# mcu.net
KiCad netlist of a schematic drawn in Altium Designer
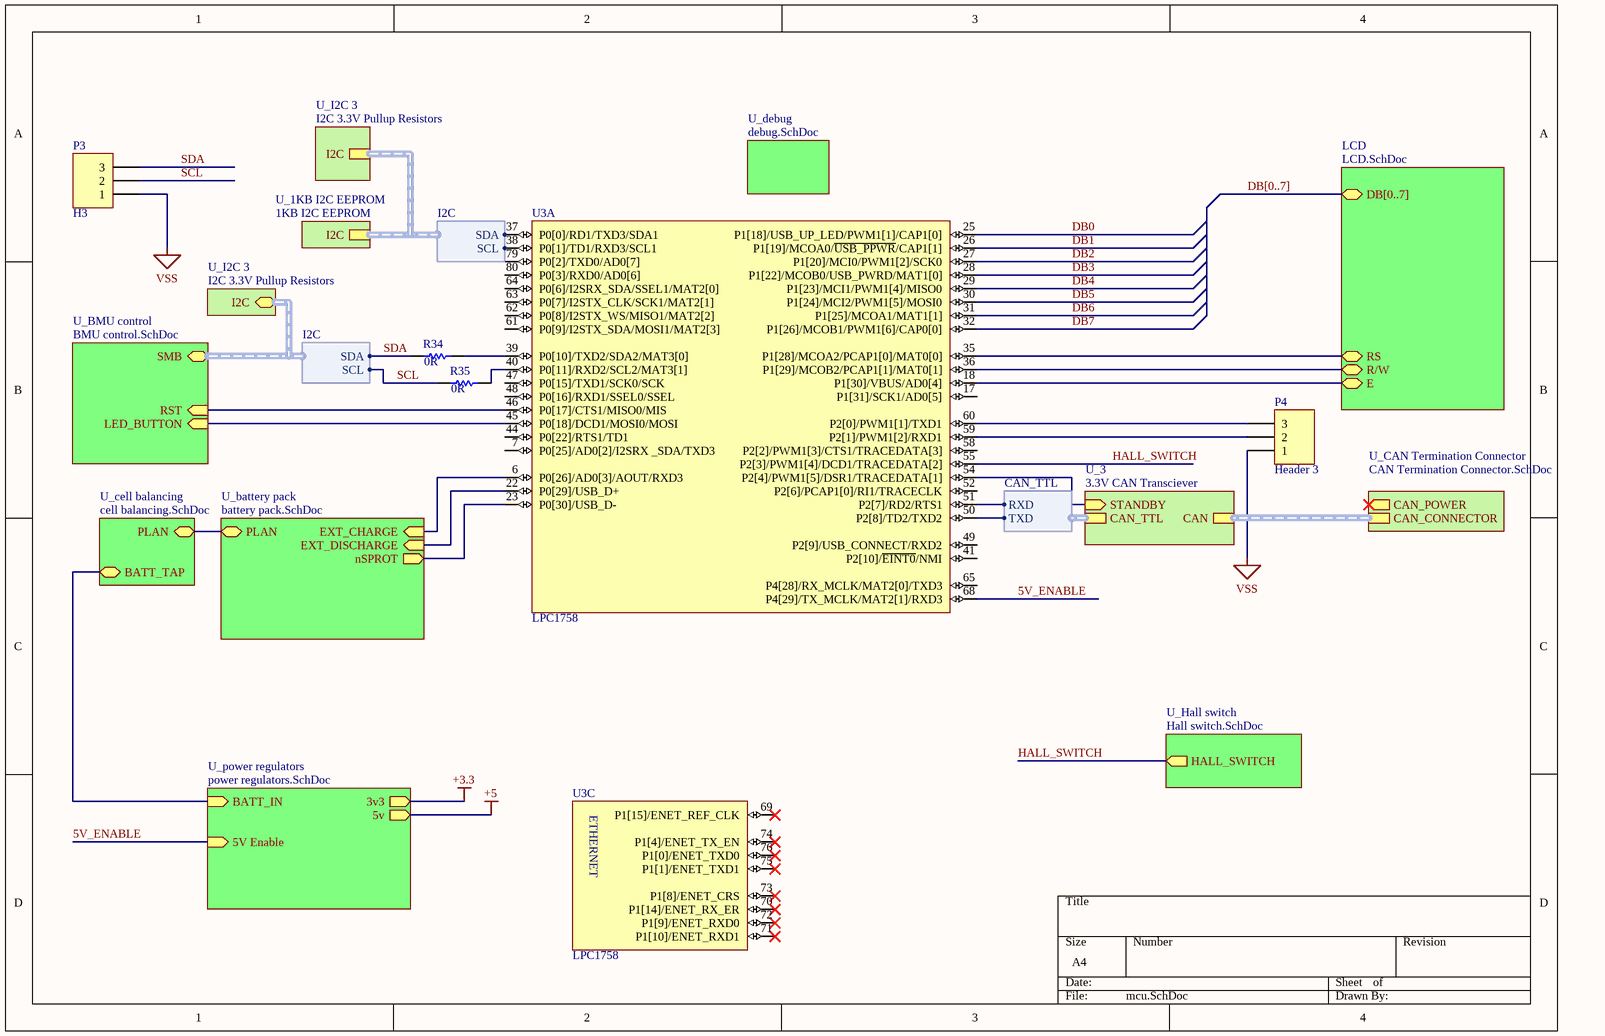
[diagram p0: mcu.SchDoc]

(export (version "E")
  (design (tool "Eeschema 10.0.6"))
  (components
    (comp (ref "P3")
      (value "H3")
      (footprint "HDR1X3")
      (description "Header, 3-Pin")
      (fields (field (name "PUBLISHER") "Altium Limited"))
      (libsource (lib "TXS0108E") (part "TXS0108E"))
    )
    (comp (ref "P4")
      (value "Header 3")
      (footprint "HDR1X3")
      (description "Header, 3-Pin")
      (fields (field (name "PUBLISHER") "Altium Limited"))
      (libsource (lib "Miscellaneous Connectors") (part "Header 3"))
    )
    (comp (ref "R34")
      (value "0R")
      (footprint "R0603")
      (description "Resistor")
      (fields (field (name "Comment") "Res1") (field (name "PUBLISHER") "Altium Limited"))
      (libsource (lib "Miscellaneous Devices") (part "Res1"))
    )
    (comp (ref "R35")
      (value "0R")
      (footprint "R0603")
      (description "Resistor")
      (fields (field (name "Comment") "Res1") (field (name "PUBLISHER") "Altium Limited"))
      (libsource (lib "Miscellaneous Devices") (part "Res1"))
    )
    (comp (ref "U3")
      (value "LPC1758")
      (footprint "LPC1758FBD80")
      (description "NXP - LPC1758FBD80 - MCU, 32BIT, ARM CORTEX M3, 80LQFP")
      (libsource (lib "LPC1758") (part "LPC1758"))
    )
  )
  (nets
    (net (code "5") (name "/5V_ENABLE") (class "Default")
      (node (ref "U3") (pin "68") (pinfunction "P4[29]/TX_MCLK/MAT2[1]/RXD3_68") (pintype "bidirectional"))
    )
    (net (code "9") (name "/DB0") (class "Default")
      (node (ref "U3") (pin "25") (pinfunction "P1[18]/USB_UP_LED/PWM1[1]/CAP1[0]_25") (pintype "bidirectional"))
    )
    (net (code "10") (name "/DB1") (class "Default")
      (node (ref "U3") (pin "26") (pinfunction "P1[19]/MCOA0/~{USB_PPWR}/CAP1[1]_26") (pintype "bidirectional"))
    )
    (net (code "11") (name "/DB2") (class "Default")
      (node (ref "U3") (pin "27") (pinfunction "P1[20]/MCI0/PWM1[2]/SCK0_27") (pintype "bidirectional"))
    )
    (net (code "12") (name "/DB3") (class "Default")
      (node (ref "U3") (pin "28") (pinfunction "P1[22]/MCOB0/USB_PWRD/MAT1[0]_28") (pintype "bidirectional"))
    )
    (net (code "13") (name "/DB4") (class "Default")
      (node (ref "U3") (pin "29") (pinfunction "P1[23]/MCI1/PWM1[4]/MISO0_29") (pintype "bidirectional"))
    )
    (net (code "14") (name "/DB5") (class "Default")
      (node (ref "U3") (pin "30") (pinfunction "P1[24]/MCI2/PWM1[5]/MOSI0_30") (pintype "bidirectional"))
    )
    (net (code "15") (name "/DB6") (class "Default")
      (node (ref "U3") (pin "31") (pinfunction "P1[25]/MCOA1/MAT1[1]_31") (pintype "bidirectional"))
    )
    (net (code "16") (name "/DB7") (class "Default")
      (node (ref "U3") (pin "32") (pinfunction "P1[26]/MCOB1/PWM1[6]/CAP0[0]_32") (pintype "bidirectional"))
    )
    (net (code "18") (name "/E") (class "Default")
      (node (ref "U3") (pin "18") (pinfunction "P1[30]/VBUS/AD0[4]_18") (pintype "bidirectional"))
    )
    (net (code "19") (name "/EXT_CHARGE") (class "Default")
      (node (ref "U3") (pin "6") (pinfunction "P0[26]/AD0[3]/AOUT/RXD3_6") (pintype "bidirectional"))
    )
    (net (code "20") (name "/EXT_DISCHARGE") (class "Default")
      (node (ref "U3") (pin "22") (pinfunction "P0[29]/USB_D+_22") (pintype "bidirectional"))
    )
    (net (code "21") (name "/HALL_SWITCH") (class "Default")
      (node (ref "U3") (pin "55") (pinfunction "P2[3]/PWM1[4]/DCD1/TRACEDATA[2]_55") (pintype "bidirectional"))
    )
    (net (code "24") (name "/LED_BUTTON") (class "Default")
      (node (ref "U3") (pin "45") (pinfunction "P0[18]/DCD1/MOSI0/MOSI_45") (pintype "bidirectional"))
    )
    (net (code "26") (name "/RS") (class "Default")
      (node (ref "U3") (pin "35") (pinfunction "P1[28]/MCOA2/PCAP1[0]/MAT0[0]_35") (pintype "bidirectional"))
    )
    (net (code "27") (name "/RST") (class "Default")
      (node (ref "U3") (pin "46") (pinfunction "P0[17]/CTS1/MISO0/MIS_46") (pintype "bidirectional"))
    )
    (net (code "28") (name "/RXD") (class "Default")
      (node (ref "U3") (pin "51") (pinfunction "P2[7]/RD2/RTS1_51") (pintype "bidirectional"))
    )
    (net (code "29") (name "/R{slash}W") (class "Default")
      (node (ref "U3") (pin "36") (pinfunction "P1[29]/MCOB2/PCAP1[1]/MAT0[1]_36") (pintype "bidirectional"))
    )
    (net (code "30") (name "/SCL") (class "Default")
      (node (ref "P3") (pin "2") (pinfunction "2_2") (pintype "passive"))
      (node (ref "R35") (pin "1") (pinfunction "1_1") (pintype "passive"))
    )
    (net (code "31") (name "/SDA") (class "Default")
      (node (ref "P3") (pin "3") (pinfunction "3_3") (pintype "passive"))
      (node (ref "R34") (pin "1") (pinfunction "1_1") (pintype "passive"))
    )
    (net (code "32") (name "/STANDBY") (class "Default")
      (node (ref "U3") (pin "54") (pinfunction "P2[4]/PWM1[5]/DSR1/TRACEDATA[1]_54") (pintype "bidirectional"))
    )
    (net (code "33") (name "/TXD") (class "Default")
      (node (ref "U3") (pin "50") (pinfunction "P2[8]/TD2/TXD2_50") (pintype "bidirectional"))
    )
    (net (code "34") (name "/nSPROT") (class "Default")
      (node (ref "U3") (pin "23") (pinfunction "P0[30]/USB_D-_23") (pintype "bidirectional"))
    )
    (net (code "37") (name "Net-(U3A-P0[10]{slash}TXD2{slash}SDA2{slash}MAT3[0])") (class "Default")
      (node (ref "R34") (pin "2") (pinfunction "2_2") (pintype "passive"))
      (node (ref "U3") (pin "39") (pinfunction "P0[10]/TXD2/SDA2/MAT3[0]_39") (pintype "bidirectional"))
    )
    (net (code "38") (name "Net-(U3A-P0[11]{slash}RXD2{slash}SCL2{slash}MAT3[1])") (class "Default")
      (node (ref "R35") (pin "2") (pinfunction "2_2") (pintype "passive"))
      (node (ref "U3") (pin "40") (pinfunction "P0[11]/RXD2/SCL2/MAT3[1]_40") (pintype "bidirectional"))
    )
    (net (code "39") (name "Net-(U3A-P2[0]{slash}PWM1[1]{slash}TXD1)") (class "Default")
      (node (ref "P4") (pin "3") (pinfunction "3_3") (pintype "passive"))
      (node (ref "U3") (pin "60") (pinfunction "P2[0]/PWM1[1]/TXD1_60") (pintype "bidirectional"))
    )
    (net (code "40") (name "Net-(U3A-P2[1]{slash}PWM1[2]{slash}RXD1)") (class "Default")
      (node (ref "P4") (pin "2") (pinfunction "2_2") (pintype "passive"))
      (node (ref "U3") (pin "59") (pinfunction "P2[1]/PWM1[2]/RXD1_59") (pintype "bidirectional"))
    )
    (net (code "41") (name "VSS") (class "Default")
      (node (ref "P3") (pin "1") (pinfunction "1_1") (pintype "passive"))
      (node (ref "P4") (pin "1") (pinfunction "1_1") (pintype "passive"))
    )
    (net (code "42") (name "unconnected-(U3A-P0[0]{slash}RD1{slash}TXD3{slash}SDA1-Pad37)") (class "Default")
      (node (ref "U3") (pin "37") (pinfunction "P0[0]/RD1/TXD3/SDA1_37") (pintype "bidirectional"))
    )
    (net (code "43") (name "unconnected-(U3A-P0[1]{slash}TD1{slash}RXD3{slash}SCL1-Pad38)") (class "Default")
      (node (ref "U3") (pin "38") (pinfunction "P0[1]/TD1/RXD3/SCL1_38") (pintype "bidirectional"))
    )
    (net (code "44") (name "unconnected-(U3A-P0[2]{slash}TXD0{slash}AD0[7]-Pad79)") (class "Default")
      (node (ref "U3") (pin "79") (pinfunction "P0[2]/TXD0/AD0[7]_79") (pintype "bidirectional"))
    )
    (net (code "45") (name "unconnected-(U3A-P0[3]{slash}RXD0{slash}AD0[6]-Pad80)") (class "Default")
      (node (ref "U3") (pin "80") (pinfunction "P0[3]/RXD0/AD0[6]_80") (pintype "bidirectional"))
    )
    (net (code "46") (name "unconnected-(U3A-P0[6]{slash}I2SRX_SDA{slash}SSEL1{slash}MAT2[0]-Pad64)") (class "Default")
      (node (ref "U3") (pin "64") (pinfunction "P0[6]/I2SRX_SDA/SSEL1/MAT2[0]_64") (pintype "bidirectional"))
    )
    (net (code "47") (name "unconnected-(U3A-P0[7]{slash}I2STX_CLK{slash}SCK1{slash}MAT2[1]-Pad63)") (class "Default")
      (node (ref "U3") (pin "63") (pinfunction "P0[7]/I2STX_CLK/SCK1/MAT2[1]_63") (pintype "bidirectional"))
    )
    (net (code "48") (name "unconnected-(U3A-P0[8]{slash}I2STX_WS{slash}MISO1{slash}MAT2[2]-Pad62)") (class "Default")
      (node (ref "U3") (pin "62") (pinfunction "P0[8]/I2STX_WS/MISO1/MAT2[2]_62") (pintype "bidirectional"))
    )
    (net (code "49") (name "unconnected-(U3A-P0[9]{slash}I2STX_SDA{slash}MOSI1{slash}MAT2[3]-Pad61)") (class "Default")
      (node (ref "U3") (pin "61") (pinfunction "P0[9]/I2STX_SDA/MOSI1/MAT2[3]_61") (pintype "bidirectional"))
    )
    (net (code "50") (name "unconnected-(U3A-P0[15]{slash}TXD1{slash}SCK0{slash}SCK-Pad47)") (class "Default")
      (node (ref "U3") (pin "47") (pinfunction "P0[15]/TXD1/SCK0/SCK_47") (pintype "bidirectional"))
    )
    (net (code "51") (name "unconnected-(U3A-P0[16]{slash}RXD1{slash}SSEL0{slash}SSEL-Pad48)") (class "Default")
      (node (ref "U3") (pin "48") (pinfunction "P0[16]/RXD1/SSEL0/SSEL_48") (pintype "bidirectional"))
    )
    (net (code "52") (name "unconnected-(U3A-P0[22]{slash}RTS1{slash}TD1-Pad44)") (class "Default")
      (node (ref "U3") (pin "44") (pinfunction "P0[22]/RTS1/TD1_44") (pintype "bidirectional"))
    )
    (net (code "53") (name "unconnected-(U3A-P0[25]{slash}AD0[2]{slash}I2SRX__SDA{slash}TXD3-Pad7)") (class "Default")
      (node (ref "U3") (pin "7") (pinfunction "P0[25]/AD0[2]/I2SRX__SDA/TXD3_7") (pintype "bidirectional"))
    )
    (net (code "54") (name "unconnected-(U3A-P1[31]{slash}SCK1{slash}AD0[5]-Pad17)") (class "Default")
      (node (ref "U3") (pin "17") (pinfunction "P1[31]/SCK1/AD0[5]_17") (pintype "bidirectional"))
    )
    (net (code "55") (name "unconnected-(U3A-P2[2]{slash}PWM1[3]{slash}CTS1{slash}TRACEDATA[3]-Pad58)") (class "Default")
      (node (ref "U3") (pin "58") (pinfunction "P2[2]/PWM1[3]/CTS1/TRACEDATA[3]_58") (pintype "bidirectional"))
    )
    (net (code "56") (name "unconnected-(U3A-P2[6]{slash}PCAP1[0]{slash}RI1{slash}TRACECLK-Pad52)") (class "Default")
      (node (ref "U3") (pin "52") (pinfunction "P2[6]/PCAP1[0]/RI1/TRACECLK_52") (pintype "bidirectional"))
    )
    (net (code "57") (name "unconnected-(U3A-P2[9]{slash}USB_CONNECT{slash}RXD2-Pad49)") (class "Default")
      (node (ref "U3") (pin "49") (pinfunction "P2[9]/USB_CONNECT/RXD2_49") (pintype "bidirectional"))
    )
    (net (code "58") (name "unconnected-(U3A-P2[10]{slash}~{EINT0}{slash}NMI-Pad41)") (class "Default")
      (node (ref "U3") (pin "41") (pinfunction "P2[10]/~{EINT0}/NMI_41") (pintype "bidirectional"))
    )
    (net (code "59") (name "unconnected-(U3A-P4[28]{slash}RX_MCLK{slash}MAT2[0]{slash}TXD3-Pad65)") (class "Default")
      (node (ref "U3") (pin "65") (pinfunction "P4[28]/RX_MCLK/MAT2[0]/TXD3_65") (pintype "bidirectional"))
    )
    (net (code "60") (name "unconnected-(U3C-P1[0]{slash}ENET_TXD0-Pad76)") (class "Default")
      (node (ref "U3") (pin "76") (pinfunction "P1[0]/ENET_TXD0_76") (pintype "bidirectional+no_connect"))
    )
    (net (code "61") (name "unconnected-(U3C-P1[1]{slash}ENET_TXD1-Pad75)") (class "Default")
      (node (ref "U3") (pin "75") (pinfunction "P1[1]/ENET_TXD1_75") (pintype "bidirectional+no_connect"))
    )
    (net (code "62") (name "unconnected-(U3C-P1[4]{slash}ENET_TX_EN-Pad74)") (class "Default")
      (node (ref "U3") (pin "74") (pinfunction "P1[4]/ENET_TX_EN_74") (pintype "bidirectional+no_connect"))
    )
    (net (code "63") (name "unconnected-(U3C-P1[8]{slash}ENET_CRS-Pad73)") (class "Default")
      (node (ref "U3") (pin "73") (pinfunction "P1[8]/ENET_CRS_73") (pintype "bidirectional+no_connect"))
    )
    (net (code "64") (name "unconnected-(U3C-P1[9]{slash}ENET_RXD0-Pad72)") (class "Default")
      (node (ref "U3") (pin "72") (pinfunction "P1[9]/ENET_RXD0_72") (pintype "bidirectional+no_connect"))
    )
    (net (code "65") (name "unconnected-(U3C-P1[10]{slash}ENET_RXD1-Pad71)") (class "Default")
      (node (ref "U3") (pin "71") (pinfunction "P1[10]/ENET_RXD1_71") (pintype "bidirectional+no_connect"))
    )
    (net (code "66") (name "unconnected-(U3C-P1[14]{slash}ENET_RX_ER-Pad70)") (class "Default")
      (node (ref "U3") (pin "70") (pinfunction "P1[14]/ENET_RX_ER_70") (pintype "bidirectional+no_connect"))
    )
    (net (code "67") (name "unconnected-(U3C-P1[15]{slash}ENET_REF_CLK-Pad69)") (class "Default")
      (node (ref "U3") (pin "69") (pinfunction "P1[15]/ENET_REF_CLK_69") (pintype "bidirectional+no_connect"))
    )
  )
)
